# PSU-rev_02.net
KiCad netlist of a schematic drawn in EAGLE
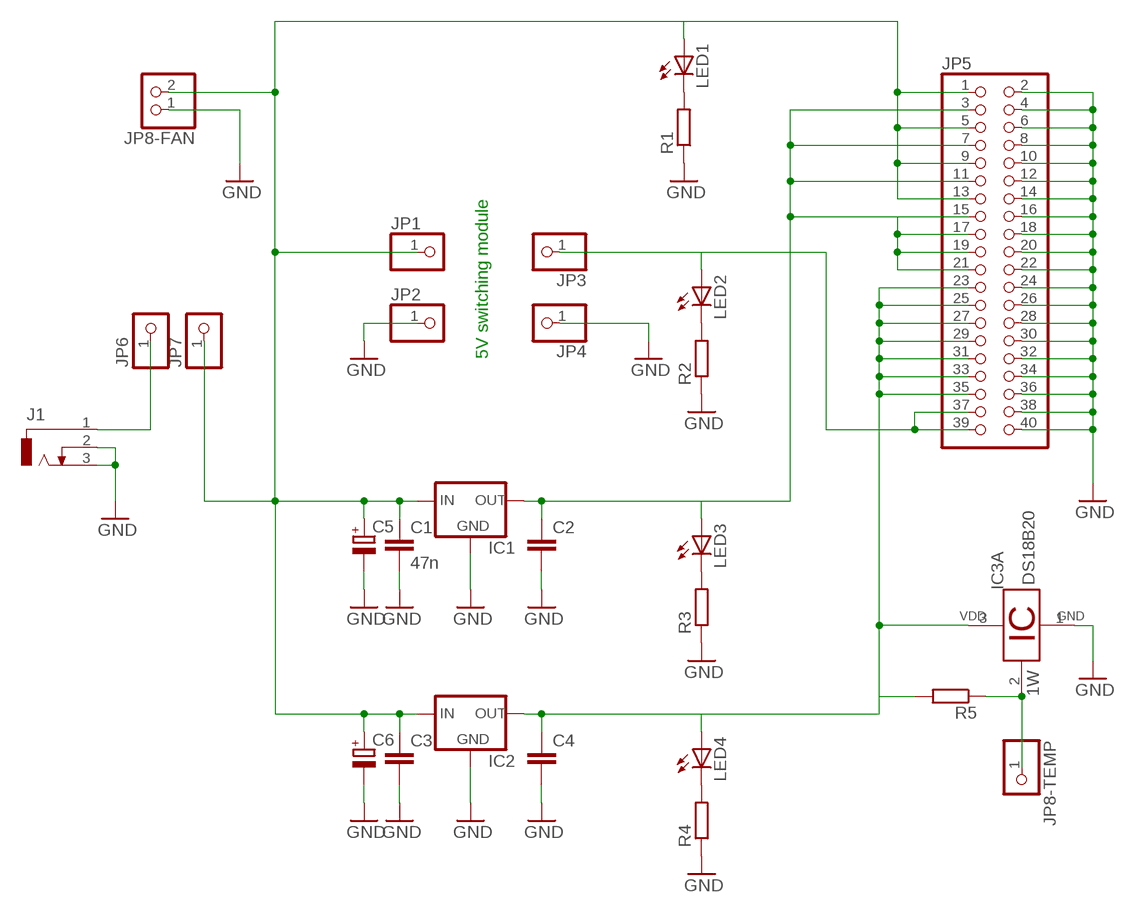
[diagram p0: schematic, sheet 1]

(export (version "E")
  (design (tool "Eeschema 10.0.6"))
  (components
    (comp (ref "C1")
      (value "47n")
      (footprint "eagle-import:C050-024X044")
      (libsource (lib "eagle-import") (part "C-EU050-024X044"))
    )
    (comp (ref "C2")
      (value "C-EU050-024X044")
      (footprint "eagle-import:C050-024X044")
      (libsource (lib "eagle-import") (part "C-EU050-024X044"))
    )
    (comp (ref "C3")
      (value "C-EU050-024X044")
      (footprint "eagle-import:C050-024X044")
      (libsource (lib "eagle-import") (part "C-EU050-024X044"))
    )
    (comp (ref "C4")
      (value "C-EU050-024X044")
      (footprint "eagle-import:C050-024X044")
      (libsource (lib "eagle-import") (part "C-EU050-024X044"))
    )
    (comp (ref "C5")
      (value "CPOL-EUE3.5-8")
      (footprint "eagle-import:E3,5-8")
      (libsource (lib "eagle-import") (part "CPOL-EUE3.5-8"))
    )
    (comp (ref "C6")
      (value "CPOL-EUE3.5-8")
      (footprint "eagle-import:E3,5-8")
      (libsource (lib "eagle-import") (part "CPOL-EUE3.5-8"))
    )
    (comp (ref "IC1")
      (value "78XXL")
      (footprint "eagle-import:78XXL")
      (libsource (lib "eagle-import") (part "78XXL"))
    )
    (comp (ref "IC2")
      (value "78XXL")
      (footprint "eagle-import:78XXL")
      (libsource (lib "eagle-import") (part "78XXL"))
    )
    (comp (ref "IC3")
      (value "DS18B20")
      (footprint "eagle-import:TO92-")
      (libsource (lib "eagle-import") (part "DS18B20"))
    )
    (comp (ref "J1")
      (value "DCJ0303")
      (footprint "eagle-import:DCJ0303")
      (libsource (lib "eagle-import") (part "DCJ0303"))
    )
    (comp (ref "JP1")
      (value "PINHD-1X1")
      (footprint "eagle-import:1X01")
      (libsource (lib "eagle-import") (part "PINHD-1X1"))
    )
    (comp (ref "JP2")
      (value "PINHD-1X1")
      (footprint "eagle-import:1X01")
      (libsource (lib "eagle-import") (part "PINHD-1X1"))
    )
    (comp (ref "JP3")
      (value "PINHD-1X1")
      (footprint "eagle-import:1X01")
      (libsource (lib "eagle-import") (part "PINHD-1X1"))
    )
    (comp (ref "JP4")
      (value "PINHD-1X1")
      (footprint "eagle-import:1X01")
      (libsource (lib "eagle-import") (part "PINHD-1X1"))
    )
    (comp (ref "JP5")
      (value "PINHD-2X20")
      (footprint "eagle-import:2X20")
      (libsource (lib "eagle-import") (part "PINHD-2X20"))
    )
    (comp (ref "JP6")
      (value "PINHD-1X1")
      (footprint "eagle-import:1X01")
      (libsource (lib "eagle-import") (part "PINHD-1X1"))
    )
    (comp (ref "JP7")
      (value "PINHD-1X1")
      (footprint "eagle-import:1X01")
      (libsource (lib "eagle-import") (part "PINHD-1X1"))
    )
    (comp (ref "JP8-FAN")
      (value "PINHD-1X2")
      (footprint "eagle-import:1X02")
      (libsource (lib "eagle-import") (part "PINHD-1X2"))
    )
    (comp (ref "JP8-TEMP")
      (value "PINHD-1X1")
      (footprint "eagle-import:1X01")
      (libsource (lib "eagle-import") (part "PINHD-1X1"))
    )
    (comp (ref "LED1")
      (value "LEDSML1206")
      (footprint "eagle-import:SML1206")
      (libsource (lib "eagle-import") (part "LEDSML1206"))
    )
    (comp (ref "LED2")
      (value "LEDSML1206")
      (footprint "eagle-import:SML1206")
      (libsource (lib "eagle-import") (part "LEDSML1206"))
    )
    (comp (ref "LED3")
      (value "LEDSML1206")
      (footprint "eagle-import:SML1206")
      (libsource (lib "eagle-import") (part "LEDSML1206"))
    )
    (comp (ref "LED4")
      (value "LEDSML1206")
      (footprint "eagle-import:SML1206")
      (libsource (lib "eagle-import") (part "LEDSML1206"))
    )
    (comp (ref "R1")
      (value "R-EU_R1206")
      (footprint "eagle-import:R1206")
      (libsource (lib "eagle-import") (part "R-EU_R1206"))
    )
    (comp (ref "R2")
      (value "R-EU_R1206")
      (footprint "eagle-import:R1206")
      (libsource (lib "eagle-import") (part "R-EU_R1206"))
    )
    (comp (ref "R3")
      (value "R-EU_R1206")
      (footprint "eagle-import:R1206")
      (libsource (lib "eagle-import") (part "R-EU_R1206"))
    )
    (comp (ref "R4")
      (value "R-EU_R1206")
      (footprint "eagle-import:R1206")
      (libsource (lib "eagle-import") (part "R-EU_R1206"))
    )
    (comp (ref "R5")
      (value "R-EU_R1206")
      (footprint "eagle-import:R1206")
      (libsource (lib "eagle-import") (part "R-EU_R1206"))
    )
  )
  (nets
    (net (code "1") (name "GND") (class "Default")
      (node (ref "C1") (pin "2") (pinfunction "2_2") (pintype "passive"))
      (node (ref "C2") (pin "2") (pinfunction "2_2") (pintype "passive"))
      (node (ref "C3") (pin "2") (pinfunction "2_2") (pintype "passive"))
      (node (ref "C4") (pin "2") (pinfunction "2_2") (pintype "passive"))
      (node (ref "C5") (pin "-") (pinfunction "-_-") (pintype "passive"))
      (node (ref "C6") (pin "-") (pinfunction "-_-") (pintype "passive"))
      (node (ref "IC1") (pin "GND") (pinfunction "GND_GND") (pintype "input"))
      (node (ref "IC2") (pin "GND") (pinfunction "GND_GND") (pintype "input"))
      (node (ref "IC3") (pin "1") (pinfunction "GND_1") (pintype "power_in"))
      (node (ref "J1") (pin "2") (pinfunction "2_2") (pintype "passive"))
      (node (ref "J1") (pin "3") (pinfunction "3_3") (pintype "passive"))
      (node (ref "JP2") (pin "1") (pinfunction "1_1") (pintype "passive"))
      (node (ref "JP4") (pin "1") (pinfunction "1_1") (pintype "passive"))
      (node (ref "JP5") (pin "10") (pinfunction "10_10") (pintype "passive"))
      (node (ref "JP5") (pin "12") (pinfunction "12_12") (pintype "passive"))
      (node (ref "JP5") (pin "14") (pinfunction "14_14") (pintype "passive"))
      (node (ref "JP5") (pin "16") (pinfunction "16_16") (pintype "passive"))
      (node (ref "JP5") (pin "18") (pinfunction "18_18") (pintype "passive"))
      (node (ref "JP5") (pin "2") (pinfunction "2_2") (pintype "passive"))
      (node (ref "JP5") (pin "20") (pinfunction "20_20") (pintype "passive"))
      (node (ref "JP5") (pin "22") (pinfunction "22_22") (pintype "passive"))
      (node (ref "JP5") (pin "24") (pinfunction "24_24") (pintype "passive"))
      (node (ref "JP5") (pin "26") (pinfunction "26_26") (pintype "passive"))
      (node (ref "JP5") (pin "28") (pinfunction "28_28") (pintype "passive"))
      (node (ref "JP5") (pin "30") (pinfunction "30_30") (pintype "passive"))
      (node (ref "JP5") (pin "32") (pinfunction "32_32") (pintype "passive"))
      (node (ref "JP5") (pin "34") (pinfunction "34_34") (pintype "passive"))
      (node (ref "JP5") (pin "36") (pinfunction "36_36") (pintype "passive"))
      (node (ref "JP5") (pin "38") (pinfunction "38_38") (pintype "passive"))
      (node (ref "JP5") (pin "4") (pinfunction "4_4") (pintype "passive"))
      (node (ref "JP5") (pin "40") (pinfunction "40_40") (pintype "passive"))
      (node (ref "JP5") (pin "6") (pinfunction "6_6") (pintype "passive"))
      (node (ref "JP5") (pin "8") (pinfunction "8_8") (pintype "passive"))
      (node (ref "JP8-FAN") (pin "1") (pinfunction "1_1") (pintype "passive"))
      (node (ref "R1") (pin "1") (pinfunction "1_1") (pintype "passive"))
      (node (ref "R2") (pin "1") (pinfunction "1_1") (pintype "passive"))
      (node (ref "R3") (pin "1") (pinfunction "1_1") (pintype "passive"))
      (node (ref "R4") (pin "1") (pinfunction "1_1") (pintype "passive"))
    )
    (net (code "2") (name "Net-(C1-Pad1)") (class "Default")
      (node (ref "C1") (pin "1") (pinfunction "1_1") (pintype "passive"))
      (node (ref "C3") (pin "1") (pinfunction "1_1") (pintype "passive"))
      (node (ref "C5") (pin "+") (pinfunction "+_+") (pintype "passive"))
      (node (ref "C6") (pin "+") (pinfunction "+_+") (pintype "passive"))
      (node (ref "IC1") (pin "IN") (pinfunction "IN_IN") (pintype "input"))
      (node (ref "IC2") (pin "IN") (pinfunction "IN_IN") (pintype "input"))
      (node (ref "JP1") (pin "1") (pinfunction "1_1") (pintype "passive"))
      (node (ref "JP5") (pin "1") (pinfunction "1_1") (pintype "passive"))
      (node (ref "JP5") (pin "13") (pinfunction "13_13") (pintype "passive"))
      (node (ref "JP5") (pin "5") (pinfunction "5_5") (pintype "passive"))
      (node (ref "JP5") (pin "9") (pinfunction "9_9") (pintype "passive"))
      (node (ref "JP7") (pin "1") (pinfunction "1_1") (pintype "passive"))
      (node (ref "JP8-FAN") (pin "2") (pinfunction "2_2") (pintype "passive"))
      (node (ref "LED1") (pin "A") (pinfunction "A_A") (pintype "passive"))
    )
    (net (code "3") (name "Net-(C2-Pad1)") (class "Default")
      (node (ref "C2") (pin "1") (pinfunction "1_1") (pintype "passive"))
      (node (ref "IC1") (pin "OUT") (pinfunction "OUT_OUT") (pintype "passive"))
      (node (ref "JP5") (pin "11") (pinfunction "11_11") (pintype "passive"))
      (node (ref "JP5") (pin "15") (pinfunction "15_15") (pintype "passive"))
      (node (ref "JP5") (pin "17") (pinfunction "17_17") (pintype "passive"))
      (node (ref "JP5") (pin "19") (pinfunction "19_19") (pintype "passive"))
      (node (ref "JP5") (pin "21") (pinfunction "21_21") (pintype "passive"))
      (node (ref "JP5") (pin "3") (pinfunction "3_3") (pintype "passive"))
      (node (ref "JP5") (pin "7") (pinfunction "7_7") (pintype "passive"))
      (node (ref "LED3") (pin "A") (pinfunction "A_A") (pintype "passive"))
    )
    (net (code "4") (name "Net-(IC3B-VDD)") (class "Default")
      (node (ref "C4") (pin "1") (pinfunction "1_1") (pintype "passive"))
      (node (ref "IC2") (pin "OUT") (pinfunction "OUT_OUT") (pintype "passive"))
      (node (ref "IC3") (pin "3") (pinfunction "VDD_3") (pintype "power_in"))
      (node (ref "JP5") (pin "23") (pinfunction "23_23") (pintype "passive"))
      (node (ref "JP5") (pin "25") (pinfunction "25_25") (pintype "passive"))
      (node (ref "JP5") (pin "27") (pinfunction "27_27") (pintype "passive"))
      (node (ref "JP5") (pin "29") (pinfunction "29_29") (pintype "passive"))
      (node (ref "JP5") (pin "31") (pinfunction "31_31") (pintype "passive"))
      (node (ref "JP5") (pin "33") (pinfunction "33_33") (pintype "passive"))
      (node (ref "JP5") (pin "35") (pinfunction "35_35") (pintype "passive"))
      (node (ref "LED4") (pin "A") (pinfunction "A_A") (pintype "passive"))
      (node (ref "R5") (pin "2") (pinfunction "2_2") (pintype "passive"))
    )
    (net (code "5") (name "Net-(IC3C-1W)") (class "Default")
      (node (ref "IC3") (pin "2") (pinfunction "1W_2") (pintype "power_in"))
      (node (ref "JP8-TEMP") (pin "1") (pinfunction "1_1") (pintype "passive"))
      (node (ref "R5") (pin "1") (pinfunction "1_1") (pintype "passive"))
    )
    (net (code "6") (name "Net-(J1-Pad1)") (class "Default")
      (node (ref "J1") (pin "1") (pinfunction "1_1") (pintype "passive"))
      (node (ref "JP6") (pin "1") (pinfunction "1_1") (pintype "passive"))
    )
    (net (code "7") (name "Net-(JP3-Pad1)") (class "Default")
      (node (ref "JP3") (pin "1") (pinfunction "1_1") (pintype "passive"))
      (node (ref "JP5") (pin "37") (pinfunction "37_37") (pintype "passive"))
      (node (ref "JP5") (pin "39") (pinfunction "39_39") (pintype "passive"))
      (node (ref "LED2") (pin "A") (pinfunction "A_A") (pintype "passive"))
    )
    (net (code "8") (name "Net-(LED1-PadC)") (class "Default")
      (node (ref "LED1") (pin "C") (pinfunction "C_C") (pintype "passive"))
      (node (ref "R1") (pin "2") (pinfunction "2_2") (pintype "passive"))
    )
    (net (code "9") (name "Net-(LED2-PadC)") (class "Default")
      (node (ref "LED2") (pin "C") (pinfunction "C_C") (pintype "passive"))
      (node (ref "R2") (pin "2") (pinfunction "2_2") (pintype "passive"))
    )
    (net (code "10") (name "Net-(LED3-PadC)") (class "Default")
      (node (ref "LED3") (pin "C") (pinfunction "C_C") (pintype "passive"))
      (node (ref "R3") (pin "2") (pinfunction "2_2") (pintype "passive"))
    )
    (net (code "11") (name "Net-(LED4-PadC)") (class "Default")
      (node (ref "LED4") (pin "C") (pinfunction "C_C") (pintype "passive"))
      (node (ref "R4") (pin "2") (pinfunction "2_2") (pintype "passive"))
    )
  )
)
